# Amp_op2.net
KiCad netlist of a schematic drawn in Altium Designer
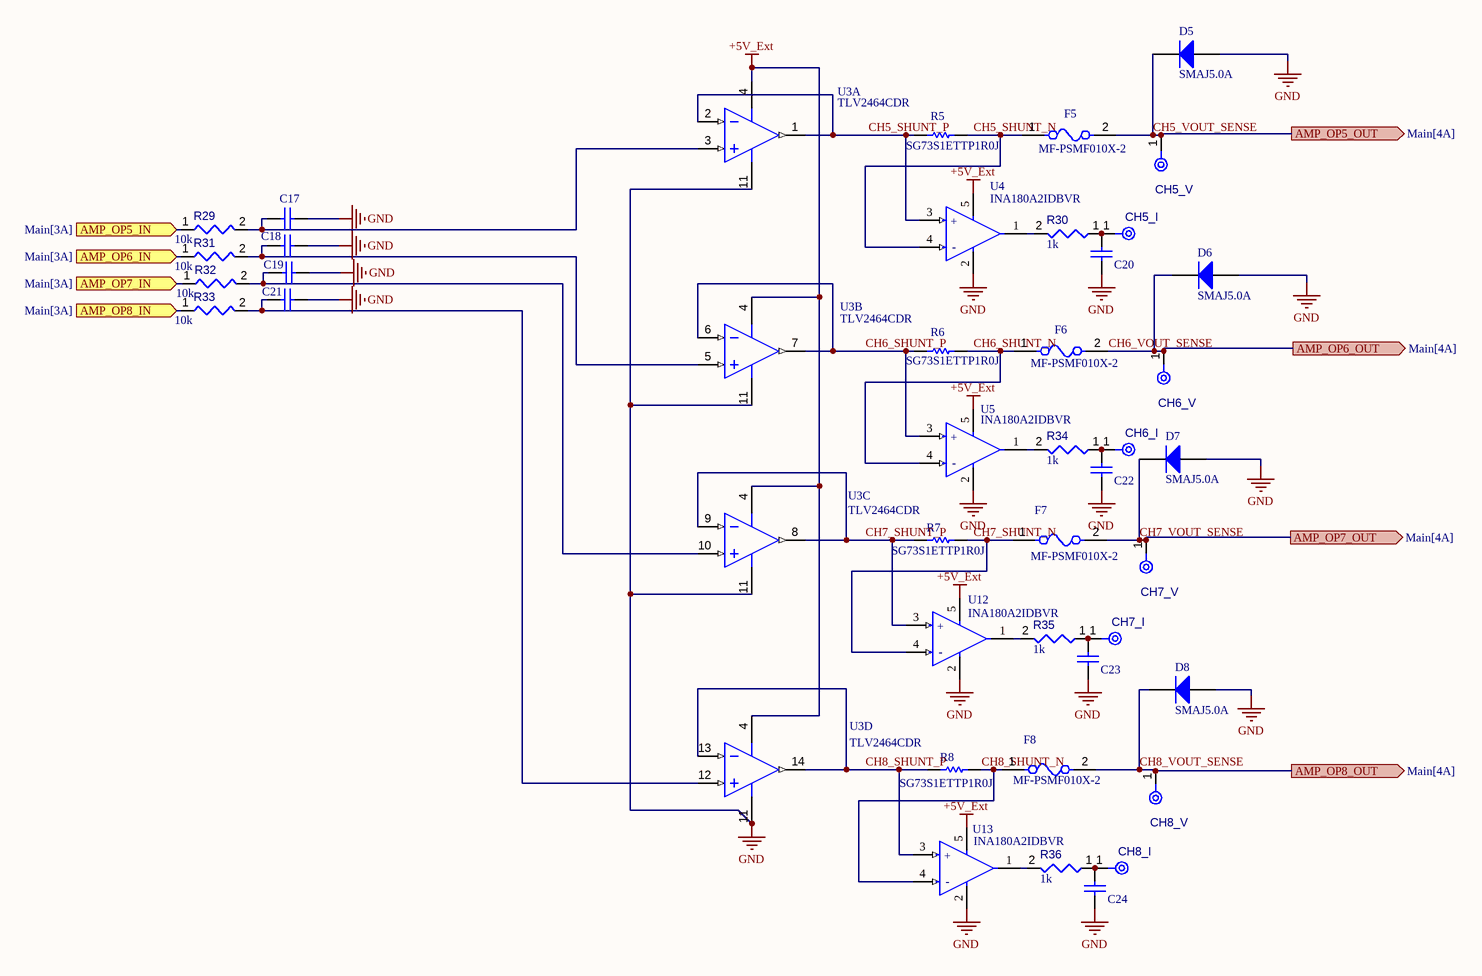
[diagram p0: Amp_op2.SchDoc]

(export (version "E")
  (design (tool "Eeschema 10.0.6"))
  (components
    (comp (ref "C17")
      (value "VJ0603Y104MXJCW1BC")
      (footprint "CAPC1608X95X40NL15T15")
      (fields (field (name "MANUFACTURER") "Vitramon"))
      (libsource (lib "Altium Content Vault") (part "CAP"))
    )
    (comp (ref "C18")
      (value "VJ0603Y104MXJCW1BC")
      (footprint "CAPC1608X95X40NL15T15")
      (fields (field (name "MANUFACTURER") "Vitramon"))
      (libsource (lib "Altium Content Vault") (part "CAP"))
    )
    (comp (ref "C19")
      (value "VJ0603Y104MXJCW1BC")
      (footprint "CAPC1608X95X40NL15T15")
      (fields (field (name "MANUFACTURER") "Vitramon"))
      (libsource (lib "Altium Content Vault") (part "CAP"))
    )
    (comp (ref "C20")
      (value "VJ0603Y104MXJCW1BC")
      (footprint "CAPC1608X95X40NL15T15")
      (fields (field (name "MANUFACTURER") "Vitramon"))
      (libsource (lib "Altium Content Vault") (part "CAP"))
    )
    (comp (ref "C21")
      (value "VJ0603Y104MXJCW1BC")
      (footprint "CAPC1608X95X40NL15T15")
      (fields (field (name "MANUFACTURER") "Vitramon"))
      (libsource (lib "Altium Content Vault") (part "CAP"))
    )
    (comp (ref "C22")
      (value "VJ0603Y104MXJCW1BC")
      (footprint "CAPC1608X95X40NL15T15")
      (fields (field (name "MANUFACTURER") "Vitramon"))
      (libsource (lib "Altium Content Vault") (part "CAP"))
    )
    (comp (ref "C23")
      (value "VJ0603Y104MXJCW1BC")
      (footprint "CAPC1608X95X40NL15T15")
      (fields (field (name "MANUFACTURER") "Vitramon"))
      (libsource (lib "Altium Content Vault") (part "CAP"))
    )
    (comp (ref "C24")
      (value "VJ0603Y104MXJCW1BC")
      (footprint "CAPC1608X95X40NL15T15")
      (fields (field (name "MANUFACTURER") "Vitramon"))
      (libsource (lib "Altium Content Vault") (part "CAP"))
    )
    (comp (ref "CH5_I")
      (value "TPAD6R")
      (footprint "TP06R")
      (description "0.6mm round")
      (libsource (lib "PCEIOT") (part "CMP-00028-00002-2"))
    )
    (comp (ref "CH5_V")
      (value "TPAD6R")
      (footprint "TP06R")
      (description "0.6mm round")
      (libsource (lib "PCEIOT") (part "CMP-00028-00002-2"))
    )
    (comp (ref "CH6_I")
      (value "TPAD6R")
      (footprint "TP06R")
      (description "0.6mm round")
      (libsource (lib "PCEIOT") (part "CMP-00028-00002-2"))
    )
    (comp (ref "CH6_V")
      (value "TPAD6R")
      (footprint "TP06R")
      (description "0.6mm round")
      (libsource (lib "PCEIOT") (part "CMP-00028-00002-2"))
    )
    (comp (ref "CH7_I")
      (value "TPAD6R")
      (footprint "TP06R")
      (description "0.6mm round")
      (libsource (lib "PCEIOT") (part "CMP-00028-00002-2"))
    )
    (comp (ref "CH7_V")
      (value "TPAD6R")
      (footprint "TP06R")
      (description "0.6mm round")
      (libsource (lib "PCEIOT") (part "CMP-00028-00002-2"))
    )
    (comp (ref "CH8_I")
      (value "TPAD6R")
      (footprint "TP06R")
      (description "0.6mm round")
      (libsource (lib "PCEIOT") (part "CMP-00028-00002-2"))
    )
    (comp (ref "CH8_V")
      (value "TPAD6R")
      (footprint "TP06R")
      (description "0.6mm round")
      (libsource (lib "PCEIOT") (part "CMP-00028-00002-2"))
    )
    (comp (ref "D5")
      (value "SMAJ5.0A")
      (footprint "BOUR-SMA-2_V")
      (fields (field (name "MANUFACTURER") "Bourns"))
      (libsource (lib "Altium Content Vault") (part "D-AK-2"))
    )
    (comp (ref "D6")
      (value "SMAJ5.0A")
      (footprint "BOUR-SMA-2_V")
      (fields (field (name "MANUFACTURER") "Bourns"))
      (libsource (lib "Altium Content Vault") (part "D-AK-2"))
    )
    (comp (ref "D7")
      (value "SMAJ5.0A")
      (footprint "BOUR-SMA-2_V")
      (fields (field (name "MANUFACTURER") "Bourns"))
      (libsource (lib "Altium Content Vault") (part "D-AK-2"))
    )
    (comp (ref "D8")
      (value "SMAJ5.0A")
      (footprint "BOUR-SMA-2_V")
      (fields (field (name "MANUFACTURER") "Bourns"))
      (libsource (lib "Altium Content Vault") (part "D-AK-2"))
    )
    (comp (ref "F5")
      (value "MF-PSMF010X-2")
      (footprint "FP-MF-PSMF-MFG")
      (description "PTC RESET FUSE 15V 100MA 0805")
      (fields
        (field (name "OCTOPART") "https://octopart.com/mf-psmf010x-2-bourns-7483441")
        (field (name "MANUFACTURER") "Bourns Inc.")
      )
      (libsource (lib "Altium Content Vault") (part "5bcf9b9f640e542cf0359d10258e979"))
    )
    (comp (ref "F6")
      (value "MF-PSMF010X-2")
      (footprint "FP-MF-PSMF-MFG")
      (description "PTC RESET FUSE 15V 100MA 0805")
      (fields
        (field (name "OCTOPART") "https://octopart.com/mf-psmf010x-2-bourns-7483441")
        (field (name "MANUFACTURER") "Bourns Inc.")
      )
      (libsource (lib "Altium Content Vault") (part "5bcf9b9f640e542cf0359d10258e979"))
    )
    (comp (ref "F7")
      (value "MF-PSMF010X-2")
      (footprint "FP-MF-PSMF-MFG")
      (description "PTC RESET FUSE 15V 100MA 0805")
      (fields
        (field (name "OCTOPART") "https://octopart.com/mf-psmf010x-2-bourns-7483441")
        (field (name "MANUFACTURER") "Bourns Inc.")
      )
      (libsource (lib "Altium Content Vault") (part "5bcf9b9f640e542cf0359d10258e979"))
    )
    (comp (ref "F8")
      (value "MF-PSMF010X-2")
      (footprint "FP-MF-PSMF-MFG")
      (description "PTC RESET FUSE 15V 100MA 0805")
      (fields
        (field (name "OCTOPART") "https://octopart.com/mf-psmf010x-2-bourns-7483441")
        (field (name "MANUFACTURER") "Bourns Inc.")
      )
      (libsource (lib "Altium Content Vault") (part "5bcf9b9f640e542cf0359d10258e979"))
    )
    (comp (ref "R5")
      (value "SG73S1ETTP1R0J")
      (footprint "RESC1005X40X25LL10T10")
      (fields (field (name "MANUFACTURER") "KOA Speer"))
      (libsource (lib "Altium Content Vault") (part "RES"))
    )
    (comp (ref "R6")
      (value "SG73S1ETTP1R0J")
      (footprint "RESC1005X40X25LL10T10")
      (fields (field (name "MANUFACTURER") "KOA Speer"))
      (libsource (lib "Altium Content Vault") (part "RES"))
    )
    (comp (ref "R7")
      (value "SG73S1ETTP1R0J")
      (footprint "RESC1005X40X25LL10T10")
      (fields (field (name "MANUFACTURER") "KOA Speer"))
      (libsource (lib "Altium Content Vault") (part "RES"))
    )
    (comp (ref "R8")
      (value "SG73S1ETTP1R0J")
      (footprint "RESC1005X40X25LL10T10")
      (fields (field (name "MANUFACTURER") "KOA Speer"))
      (libsource (lib "Altium Content Vault") (part "RES"))
    )
    (comp (ref "R29")
      (value "10k")
      (footprint "RESC0603(1608)_L")
      (description "Chip Resistor, 10 KOhm, +/- 1%, 01 W, -55 to 155 degC, 0603 (1608 Metric)")
      (fields (field (name "POWER") "100mW") (field (name "TOLERANCE") "1%"))
      (libsource (lib "PCEIOT") (part "CMP-009-00017-7"))
    )
    (comp (ref "R30")
      (value "1k")
      (footprint "RESC0603(1608)_L")
      (description "Chip Resistor, 1 KOhm, +/-1%, 0.1 W, -55 to 155 degC, 0603 (1608 Metric)")
      (fields (field (name "POWER") "100mW") (field (name "TOLERANCE") "1%"))
      (libsource (lib "PCEIOT") (part "CMP-009-00014-6"))
    )
    (comp (ref "R31")
      (value "10k")
      (footprint "RESC0603(1608)_L")
      (description "Chip Resistor, 10 KOhm, +/- 1%, 01 W, -55 to 155 degC, 0603 (1608 Metric)")
      (fields (field (name "POWER") "100mW") (field (name "TOLERANCE") "1%"))
      (libsource (lib "PCEIOT") (part "CMP-009-00017-7"))
    )
    (comp (ref "R32")
      (value "10k")
      (footprint "RESC0603(1608)_L")
      (description "Chip Resistor, 10 KOhm, +/- 1%, 01 W, -55 to 155 degC, 0603 (1608 Metric)")
      (fields (field (name "POWER") "100mW") (field (name "TOLERANCE") "1%"))
      (libsource (lib "PCEIOT") (part "CMP-009-00017-7"))
    )
    (comp (ref "R33")
      (value "10k")
      (footprint "RESC0603(1608)_L")
      (description "Chip Resistor, 10 KOhm, +/- 1%, 01 W, -55 to 155 degC, 0603 (1608 Metric)")
      (fields (field (name "POWER") "100mW") (field (name "TOLERANCE") "1%"))
      (libsource (lib "PCEIOT") (part "CMP-009-00017-7"))
    )
    (comp (ref "R34")
      (value "1k")
      (footprint "RESC0603(1608)_L")
      (description "Chip Resistor, 1 KOhm, +/-1%, 0.1 W, -55 to 155 degC, 0603 (1608 Metric)")
      (fields (field (name "POWER") "100mW") (field (name "TOLERANCE") "1%"))
      (libsource (lib "PCEIOT") (part "CMP-009-00014-6"))
    )
    (comp (ref "R35")
      (value "1k")
      (footprint "RESC0603(1608)_L")
      (description "Chip Resistor, 1 KOhm, +/-1%, 0.1 W, -55 to 155 degC, 0603 (1608 Metric)")
      (fields (field (name "POWER") "100mW") (field (name "TOLERANCE") "1%"))
      (libsource (lib "PCEIOT") (part "CMP-009-00014-6"))
    )
    (comp (ref "R36")
      (value "1k")
      (footprint "RESC0603(1608)_L")
      (description "Chip Resistor, 1 KOhm, +/-1%, 0.1 W, -55 to 155 degC, 0603 (1608 Metric)")
      (fields (field (name "POWER") "100mW") (field (name "TOLERANCE") "1%"))
      (libsource (lib "PCEIOT") (part "CMP-009-00014-6"))
    )
    (comp (ref "U3")
      (value "TLV2464CDR")
      (footprint "D0014A_N")
      (fields (field (name "MANUFACTURER") "Texas Instruments"))
      (libsource (lib "Altium Content Vault") (part "TI-TLV2464X-XX14"))
    )
    (comp (ref "U4")
      (value "INA180A2IDBVR")
      (footprint "FP-DBV0005A-MFG")
      (description "IC CURR SENSE 1 CIRCUIT SOT23-5")
      (libsource (lib "Altium Content Vault") (part "0a55cf1a948ad01a3239aec1b7efad0"))
    )
    (comp (ref "U5")
      (value "INA180A2IDBVR")
      (footprint "FP-DBV0005A-MFG")
      (description "IC CURR SENSE 1 CIRCUIT SOT23-5")
      (libsource (lib "Altium Content Vault") (part "0a55cf1a948ad01a3239aec1b7efad0"))
    )
    (comp (ref "U12")
      (value "INA180A2IDBVR")
      (footprint "FP-DBV0005A-MFG")
      (description "IC CURR SENSE 1 CIRCUIT SOT23-5")
      (libsource (lib "Altium Content Vault") (part "0a55cf1a948ad01a3239aec1b7efad0"))
    )
    (comp (ref "U13")
      (value "INA180A2IDBVR")
      (footprint "FP-DBV0005A-MFG")
      (description "IC CURR SENSE 1 CIRCUIT SOT23-5")
      (libsource (lib "Altium Content Vault") (part "0a55cf1a948ad01a3239aec1b7efad0"))
    )
  )
  (nets
    (net (code "1") (name "+5V_Ext") (class "Default")
      (node (ref "U12") (pin "5") (pinfunction "VS_5") (pintype "power_in"))
      (node (ref "U13") (pin "5") (pinfunction "VS_5") (pintype "power_in"))
      (node (ref "U3") (pin "4") (pinfunction "VDD+_4") (pintype "power_in"))
      (node (ref "U4") (pin "5") (pinfunction "VS_5") (pintype "power_in"))
      (node (ref "U5") (pin "5") (pinfunction "VS_5") (pintype "power_in"))
    )
    (net (code "2") (name "/AMP_OP5_IN") (class "Default")
      (node (ref "R29") (pin "1") (pinfunction "1_1") (pintype "passive"))
    )
    (net (code "3") (name "/AMP_OP6_IN") (class "Default")
      (node (ref "R31") (pin "1") (pinfunction "1_1") (pintype "passive"))
    )
    (net (code "4") (name "/AMP_OP7_IN") (class "Default")
      (node (ref "R32") (pin "1") (pinfunction "1_1") (pintype "passive"))
    )
    (net (code "5") (name "/AMP_OP8_IN") (class "Default")
      (node (ref "R33") (pin "1") (pinfunction "1_1") (pintype "passive"))
    )
    (net (code "6") (name "/CH5_SHUNT_N") (class "Default")
      (node (ref "F5") (pin "1") (pinfunction "1_1") (pintype "passive"))
      (node (ref "R5") (pin "2") (pinfunction "2_2") (pintype "passive"))
      (node (ref "U4") (pin "4") (pinfunction "IN-_4") (pintype "input"))
    )
    (net (code "7") (name "/CH5_SHUNT_P") (class "Default")
      (node (ref "R5") (pin "1") (pinfunction "1_1") (pintype "passive"))
      (node (ref "U3") (pin "1") (pinfunction "OUT1_1") (pintype "output"))
      (node (ref "U3") (pin "2") (pinfunction "IN1-_2") (pintype "input"))
      (node (ref "U4") (pin "3") (pinfunction "IN+_3") (pintype "input"))
    )
    (net (code "8") (name "/CH5_VOUT_SENSE") (class "Default")
      (node (ref "CH5_V") (pin "1") (pinfunction "TP_1") (pintype "passive"))
      (node (ref "D5") (pin "2") (pinfunction "K_2") (pintype "passive"))
      (node (ref "F5") (pin "2") (pinfunction "2_2") (pintype "passive"))
    )
    (net (code "9") (name "/CH6_SHUNT_N") (class "Default")
      (node (ref "F6") (pin "1") (pinfunction "1_1") (pintype "passive"))
      (node (ref "R6") (pin "2") (pinfunction "2_2") (pintype "passive"))
      (node (ref "U5") (pin "4") (pinfunction "IN-_4") (pintype "input"))
    )
    (net (code "10") (name "/CH6_SHUNT_P") (class "Default")
      (node (ref "R6") (pin "1") (pinfunction "1_1") (pintype "passive"))
      (node (ref "U3") (pin "6") (pinfunction "IN2-_6") (pintype "input"))
      (node (ref "U3") (pin "7") (pinfunction "OUT2_7") (pintype "output"))
      (node (ref "U5") (pin "3") (pinfunction "IN+_3") (pintype "input"))
    )
    (net (code "11") (name "/CH6_VOUT_SENSE") (class "Default")
      (node (ref "CH6_V") (pin "1") (pinfunction "TP_1") (pintype "passive"))
      (node (ref "D6") (pin "2") (pinfunction "K_2") (pintype "passive"))
      (node (ref "F6") (pin "2") (pinfunction "2_2") (pintype "passive"))
    )
    (net (code "12") (name "/CH7_SHUNT_N") (class "Default")
      (node (ref "F7") (pin "1") (pinfunction "1_1") (pintype "passive"))
      (node (ref "R7") (pin "2") (pinfunction "2_2") (pintype "passive"))
      (node (ref "U12") (pin "4") (pinfunction "IN-_4") (pintype "input"))
    )
    (net (code "13") (name "/CH7_SHUNT_P") (class "Default")
      (node (ref "R7") (pin "1") (pinfunction "1_1") (pintype "passive"))
      (node (ref "U12") (pin "3") (pinfunction "IN+_3") (pintype "input"))
      (node (ref "U3") (pin "8") (pinfunction "OUT3_8") (pintype "output"))
      (node (ref "U3") (pin "9") (pinfunction "IN3-_9") (pintype "input"))
    )
    (net (code "14") (name "/CH7_VOUT_SENSE") (class "Default")
      (node (ref "CH7_V") (pin "1") (pinfunction "TP_1") (pintype "passive"))
      (node (ref "D7") (pin "2") (pinfunction "K_2") (pintype "passive"))
      (node (ref "F7") (pin "2") (pinfunction "2_2") (pintype "passive"))
    )
    (net (code "15") (name "/CH8_SHUNT_N") (class "Default")
      (node (ref "F8") (pin "1") (pinfunction "1_1") (pintype "passive"))
      (node (ref "R8") (pin "2") (pinfunction "2_2") (pintype "passive"))
      (node (ref "U13") (pin "4") (pinfunction "IN-_4") (pintype "input"))
    )
    (net (code "16") (name "/CH8_SHUNT_P") (class "Default")
      (node (ref "R8") (pin "1") (pinfunction "1_1") (pintype "passive"))
      (node (ref "U13") (pin "3") (pinfunction "IN+_3") (pintype "input"))
      (node (ref "U3") (pin "13") (pinfunction "IN4-_13") (pintype "input"))
      (node (ref "U3") (pin "14") (pinfunction "OUT4_14") (pintype "output"))
    )
    (net (code "17") (name "/CH8_VOUT_SENSE") (class "Default")
      (node (ref "CH8_V") (pin "1") (pinfunction "TP_1") (pintype "passive"))
      (node (ref "D8") (pin "2") (pinfunction "K_2") (pintype "passive"))
      (node (ref "F8") (pin "2") (pinfunction "2_2") (pintype "passive"))
    )
    (net (code "18") (name "GND") (class "Default")
      (node (ref "C17") (pin "2") (pinfunction "2_2") (pintype "passive"))
      (node (ref "C18") (pin "2") (pinfunction "2_2") (pintype "passive"))
      (node (ref "C19") (pin "2") (pinfunction "2_2") (pintype "passive"))
      (node (ref "C20") (pin "2") (pinfunction "2_2") (pintype "passive"))
      (node (ref "C21") (pin "2") (pinfunction "2_2") (pintype "passive"))
      (node (ref "C22") (pin "2") (pinfunction "2_2") (pintype "passive"))
      (node (ref "C23") (pin "2") (pinfunction "2_2") (pintype "passive"))
      (node (ref "C24") (pin "2") (pinfunction "2_2") (pintype "passive"))
      (node (ref "D5") (pin "1") (pinfunction "A_1") (pintype "passive"))
      (node (ref "D6") (pin "1") (pinfunction "A_1") (pintype "passive"))
      (node (ref "D7") (pin "1") (pinfunction "A_1") (pintype "passive"))
      (node (ref "D8") (pin "1") (pinfunction "A_1") (pintype "passive"))
      (node (ref "U12") (pin "2") (pinfunction "GND_2") (pintype "power_in"))
      (node (ref "U13") (pin "2") (pinfunction "GND_2") (pintype "power_in"))
      (node (ref "U3") (pin "11") (pinfunction "GND_11") (pintype "power_in"))
      (node (ref "U4") (pin "2") (pinfunction "GND_2") (pintype "power_in"))
      (node (ref "U5") (pin "2") (pinfunction "GND_2") (pintype "power_in"))
    )
    (net (code "19") (name "Net-(CH5_I-TP)") (class "Default")
      (node (ref "C20") (pin "1") (pinfunction "1_1") (pintype "passive"))
      (node (ref "CH5_I") (pin "1") (pinfunction "TP_1") (pintype "passive"))
      (node (ref "R30") (pin "1") (pinfunction "1_1") (pintype "passive"))
    )
    (net (code "20") (name "Net-(CH6_I-TP)") (class "Default")
      (node (ref "C22") (pin "1") (pinfunction "1_1") (pintype "passive"))
      (node (ref "CH6_I") (pin "1") (pinfunction "TP_1") (pintype "passive"))
      (node (ref "R34") (pin "1") (pinfunction "1_1") (pintype "passive"))
    )
    (net (code "21") (name "Net-(CH7_I-TP)") (class "Default")
      (node (ref "C23") (pin "1") (pinfunction "1_1") (pintype "passive"))
      (node (ref "CH7_I") (pin "1") (pinfunction "TP_1") (pintype "passive"))
      (node (ref "R35") (pin "1") (pinfunction "1_1") (pintype "passive"))
    )
    (net (code "22") (name "Net-(CH8_I-TP)") (class "Default")
      (node (ref "C24") (pin "1") (pinfunction "1_1") (pintype "passive"))
      (node (ref "CH8_I") (pin "1") (pinfunction "TP_1") (pintype "passive"))
      (node (ref "R36") (pin "1") (pinfunction "1_1") (pintype "passive"))
    )
    (net (code "23") (name "Net-(U3A-IN1+)") (class "Default")
      (node (ref "C17") (pin "1") (pinfunction "1_1") (pintype "passive"))
      (node (ref "R29") (pin "2") (pinfunction "2_2") (pintype "passive"))
      (node (ref "U3") (pin "3") (pinfunction "IN1+_3") (pintype "input"))
    )
    (net (code "24") (name "Net-(U3B-IN2+)") (class "Default")
      (node (ref "C18") (pin "1") (pinfunction "1_1") (pintype "passive"))
      (node (ref "R31") (pin "2") (pinfunction "2_2") (pintype "passive"))
      (node (ref "U3") (pin "5") (pinfunction "IN2+_5") (pintype "input"))
    )
    (net (code "25") (name "Net-(U3C-IN3+)") (class "Default")
      (node (ref "C19") (pin "1") (pinfunction "1_1") (pintype "passive"))
      (node (ref "R32") (pin "2") (pinfunction "2_2") (pintype "passive"))
      (node (ref "U3") (pin "10") (pinfunction "IN3+_10") (pintype "input"))
    )
    (net (code "26") (name "Net-(U3D-IN4+)") (class "Default")
      (node (ref "C21") (pin "1") (pinfunction "1_1") (pintype "passive"))
      (node (ref "R33") (pin "2") (pinfunction "2_2") (pintype "passive"))
      (node (ref "U3") (pin "12") (pinfunction "IN4+_12") (pintype "input"))
    )
    (net (code "27") (name "Net-(U4-OUT)") (class "Default")
      (node (ref "R30") (pin "2") (pinfunction "2_2") (pintype "passive"))
      (node (ref "U4") (pin "1") (pinfunction "OUT_1") (pintype "passive"))
    )
    (net (code "28") (name "Net-(U5-OUT)") (class "Default")
      (node (ref "R34") (pin "2") (pinfunction "2_2") (pintype "passive"))
      (node (ref "U5") (pin "1") (pinfunction "OUT_1") (pintype "passive"))
    )
    (net (code "29") (name "Net-(U12-OUT)") (class "Default")
      (node (ref "R35") (pin "2") (pinfunction "2_2") (pintype "passive"))
      (node (ref "U12") (pin "1") (pinfunction "OUT_1") (pintype "passive"))
    )
    (net (code "30") (name "Net-(U13-OUT)") (class "Default")
      (node (ref "R36") (pin "2") (pinfunction "2_2") (pintype "passive"))
      (node (ref "U13") (pin "1") (pinfunction "OUT_1") (pintype "passive"))
    )
  )
)
